# PSU_VCC1V8_Buck.net
KiCad netlist of a schematic drawn in Altium Designer
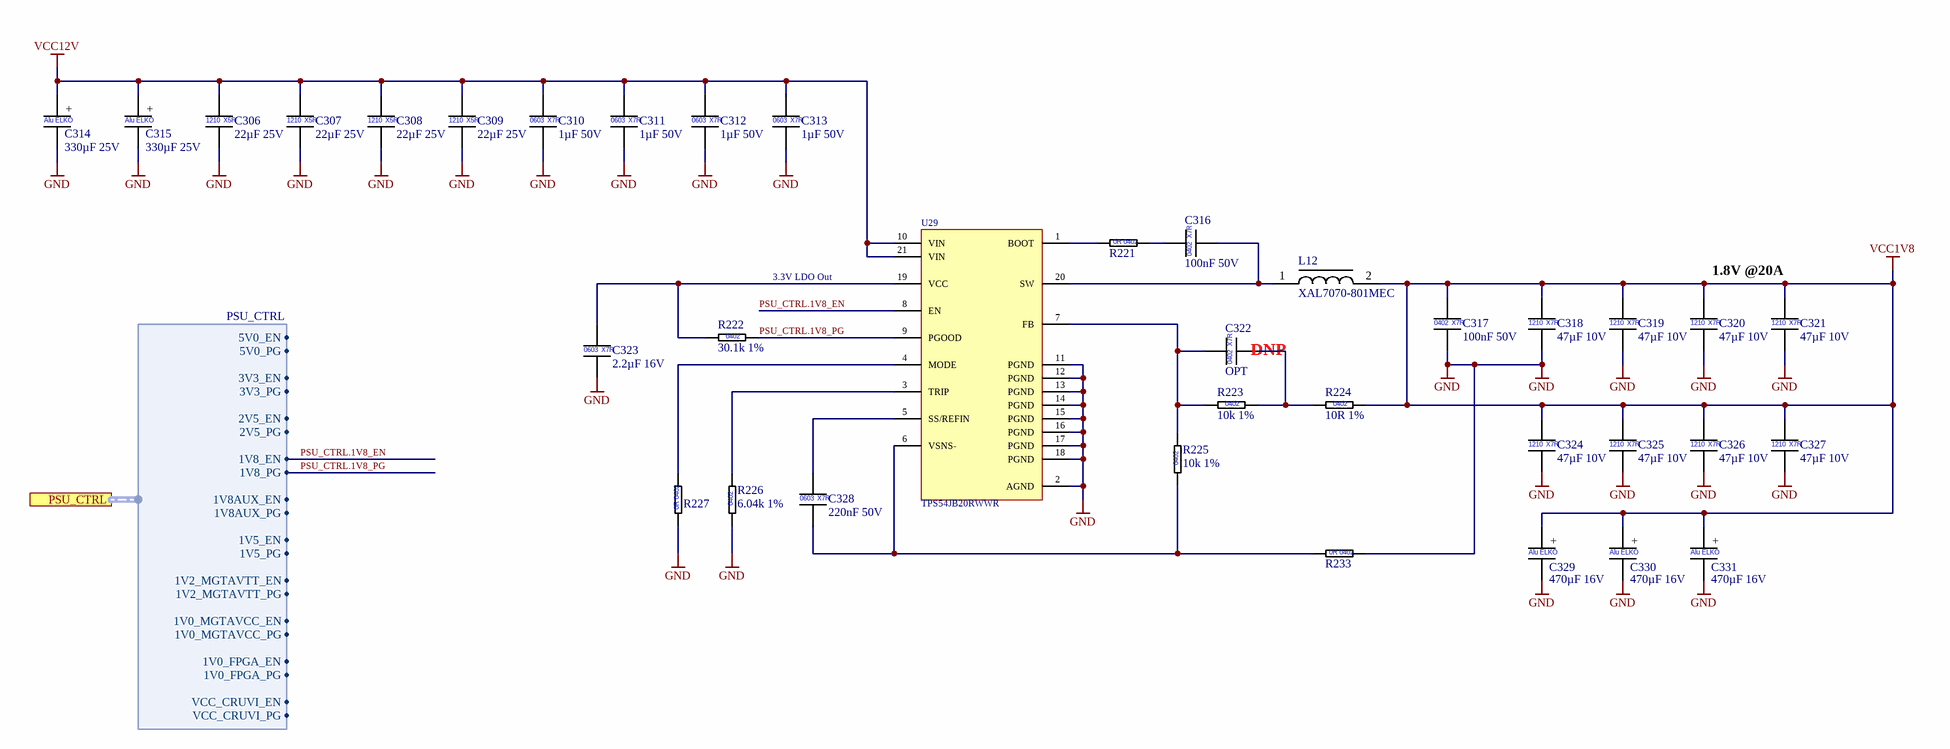
[diagram p0: PSU_VCC1V8_Buck.SchDoc]

(export (version "E")
  (design (tool "Eeschema 10.0.6"))
  (components
    (comp (ref "C306")
      (value "22µF 25V")
      (footprint "Cap:CAP_1210")
      (description "Multilayer Ceramic Capacitors MLCC - SMD/SMT 1210 25VDC")
      (libsource (lib "Cap") (part "CAP_1210_22µF_25V"))
    )
    (comp (ref "C307")
      (value "22µF 25V")
      (footprint "Cap:CAP_1210")
      (description "Multilayer Ceramic Capacitors MLCC - SMD/SMT 1210 25VDC")
      (libsource (lib "Cap") (part "CAP_1210_22µF_25V"))
    )
    (comp (ref "C308")
      (value "22µF 25V")
      (footprint "Cap:CAP_1210")
      (description "Multilayer Ceramic Capacitors MLCC - SMD/SMT 1210 25VDC")
      (libsource (lib "Cap") (part "CAP_1210_22µF_25V"))
    )
    (comp (ref "C309")
      (value "22µF 25V")
      (footprint "Cap:CAP_1210")
      (description "Multilayer Ceramic Capacitors MLCC - SMD/SMT 1210 25VDC")
      (libsource (lib "Cap") (part "CAP_1210_22µF_25V"))
    )
    (comp (ref "C310")
      (value "1µF 50V")
      (footprint "CAP_0603")
      (description "Multilayer Ceramic Capacitors MLCC - SMD/SMT 50V 1uF X7R 0603 10%")
      (libsource (lib "Cap") (part "CAP_0603_1µF_50V_X7R_10%"))
    )
    (comp (ref "C311")
      (value "1µF 50V")
      (footprint "CAP_0603")
      (description "Multilayer Ceramic Capacitors MLCC - SMD/SMT 50V 1uF X7R 0603 10%")
      (libsource (lib "Cap") (part "CAP_0603_1µF_50V_X7R_10%"))
    )
    (comp (ref "C312")
      (value "1µF 50V")
      (footprint "CAP_0603")
      (description "Multilayer Ceramic Capacitors MLCC - SMD/SMT 50V 1uF X7R 0603 10%")
      (libsource (lib "Cap") (part "CAP_0603_1µF_50V_X7R_10%"))
    )
    (comp (ref "C313")
      (value "1µF 50V")
      (footprint "CAP_0603")
      (description "Multilayer Ceramic Capacitors MLCC - SMD/SMT 50V 1uF X7R 0603 10%")
      (libsource (lib "Cap") (part "CAP_0603_1µF_50V_X7R_10%"))
    )
    (comp (ref "C314")
      (value "330µF 25V")
      (footprint "Cap:WCAP-PTG5_D10H12.5")
      (description "Organische Polymer-Aluminiumkondensatoren 330uF 25 Volts 20% AEC-Q200")
      (libsource (lib "Cap") (part "CAP_D10L12.5_330µF_25V"))
    )
    (comp (ref "C315")
      (value "330µF 25V")
      (footprint "Cap:WCAP-PTG5_D10H12.5")
      (description "Organische Polymer-Aluminiumkondensatoren 330uF 25 Volts 20% AEC-Q200")
      (libsource (lib "Cap") (part "CAP_D10L12.5_330µF_25V"))
    )
    (comp (ref "C316")
      (value "100nF 50V")
      (footprint "Cap:CAP_0402")
      (description "Multilayer Ceramic Capacitors MLCC - SMD/SMT 0402 50VDC")
      (libsource (lib "") (part "CAP_0402_100nF_50V_1"))
    )
    (comp (ref "C317")
      (value "100nF 50V")
      (footprint "Cap:CAP_0402")
      (description "Multilayer Ceramic Capacitors MLCC - SMD/SMT 0402 50VDC")
      (libsource (lib "Cap") (part "CAP_0402_100nF_50V"))
    )
    (comp (ref "C318")
      (value "47µF 10V")
      (footprint "Cap:CAP_1210")
      (description "Multilayer Ceramic Capacitors MLCC - SMD/SMT 47 uF 10 VDC 10% 1210 X7R")
      (libsource (lib "Cap") (part "CAP_1210_47µF_10V_X7R_10%"))
    )
    (comp (ref "C319")
      (value "47µF 10V")
      (footprint "Cap:CAP_1210")
      (description "Multilayer Ceramic Capacitors MLCC - SMD/SMT 47 uF 10 VDC 10% 1210 X7R")
      (libsource (lib "Cap") (part "CAP_1210_47µF_10V_X7R_10%"))
    )
    (comp (ref "C320")
      (value "47µF 10V")
      (footprint "Cap:CAP_1210")
      (description "Multilayer Ceramic Capacitors MLCC - SMD/SMT 47 uF 10 VDC 10% 1210 X7R")
      (libsource (lib "Cap") (part "CAP_1210_47µF_10V_X7R_10%"))
    )
    (comp (ref "C321")
      (value "47µF 10V")
      (footprint "Cap:CAP_1210")
      (description "Multilayer Ceramic Capacitors MLCC - SMD/SMT 47 uF 10 VDC 10% 1210 X7R")
      (libsource (lib "Cap") (part "CAP_1210_47µF_10V_X7R_10%"))
    )
    (comp (ref "C322")
      (value "OPT")
      (footprint "Cap:CAP_0402")
      (description "Multilayer Ceramic Capacitors MLCC - SMD/SMT 0402 Optional Placeholder")
      (libsource (lib "Cap") (part "CAP_0402_OPT"))
    )
    (comp (ref "C323")
      (value "2.2µF 16V")
      (footprint "Cap:CAP_0603")
      (description "Multilayer Ceramic Capacitors MLCC - SMD/SMT 2.2 uF 16 VDC 10% 0603 X7R")
      (libsource (lib "Cap") (part "CAP_0603_2.2µF_16V_X7R_10%"))
    )
    (comp (ref "C324")
      (value "47µF 10V")
      (footprint "Cap:CAP_1210")
      (description "Multilayer Ceramic Capacitors MLCC - SMD/SMT 47 uF 10 VDC 10% 1210 X7R")
      (libsource (lib "Cap") (part "CAP_1210_47µF_10V_X7R_10%"))
    )
    (comp (ref "C325")
      (value "47µF 10V")
      (footprint "Cap:CAP_1210")
      (description "Multilayer Ceramic Capacitors MLCC - SMD/SMT 47 uF 10 VDC 10% 1210 X7R")
      (libsource (lib "Cap") (part "CAP_1210_47µF_10V_X7R_10%"))
    )
    (comp (ref "C326")
      (value "47µF 10V")
      (footprint "Cap:CAP_1210")
      (description "Multilayer Ceramic Capacitors MLCC - SMD/SMT 47 uF 10 VDC 10% 1210 X7R")
      (libsource (lib "Cap") (part "CAP_1210_47µF_10V_X7R_10%"))
    )
    (comp (ref "C327")
      (value "47µF 10V")
      (footprint "Cap:CAP_1210")
      (description "Multilayer Ceramic Capacitors MLCC - SMD/SMT 47 uF 10 VDC 10% 1210 X7R")
      (libsource (lib "Cap") (part "CAP_1210_47µF_10V_X7R_10%"))
    )
    (comp (ref "C328")
      (value "220nF 50V")
      (footprint "CAP_0603")
      (description "Multilayer Ceramic Capacitors MLCC - SMD/SMT 0.22 uF 50 VDC 10% 0603 X7R")
      (libsource (lib "Cap") (part "CAP_0603_220nF_50V_X7R_10%"))
    )
    (comp (ref "C329")
      (value "470µF 16V")
      (footprint "Cap:WCAP-PTG5_D8H13")
      (description "Organische Polymer-Aluminiumkondensatoren 470uF 16 Volts 20%")
      (libsource (lib "Cap") (part "CAP_D8L9_470µF_16V"))
    )
    (comp (ref "C330")
      (value "470µF 16V")
      (footprint "Cap:WCAP-PTG5_D8H13")
      (description "Organische Polymer-Aluminiumkondensatoren 470uF 16 Volts 20%")
      (libsource (lib "Cap") (part "CAP_D8L9_470µF_16V"))
    )
    (comp (ref "C331")
      (value "470µF 16V")
      (footprint "Cap:WCAP-PTG5_D8H13")
      (description "Organische Polymer-Aluminiumkondensatoren 470uF 16 Volts 20%")
      (libsource (lib "Cap") (part "CAP_D8L9_470µF_16V"))
    )
    (comp (ref "L12")
      (value "XAL7070-801MEC")
      (footprint "indc:COILCRAFT_XAL7070")
      (description "Power Inductors - SMD 800nH Shld 20% 25.8A 2.29mOhms AECQ200")
      (libsource (lib "Indc") (part "XAL7070-801MEC_Power Inductors SMD 800nH Shld 20% 25.8A 2.29mOhms AECQ200"))
    )
    (comp (ref "R221")
      (value "0R Jumper")
      (footprint "res:RES_0402")
      (description "Thick Film Resistors - SMD 0Ohm")
      (libsource (lib "Res") (part "RES_0402_0R Jumper"))
    )
    (comp (ref "R222")
      (value "30.1k 1%")
      (footprint "res:RES_0402")
      (description "Thick Film Resistors - SMD 30.1kOhm 1%")
      (libsource (lib "Res") (part "RES_0402_30.1k_1%"))
    )
    (comp (ref "R223")
      (value "10k 1%")
      (footprint "Res:RES_0402")
      (description "Thick Film Resistors - SMD 10kOhm 1%")
      (libsource (lib "Res") (part "RES_0402_10k_1%"))
    )
    (comp (ref "R224")
      (value "10R 1%")
      (footprint "res:RES_0402")
      (description "Thick Film Resistors - SMD 10Ohm 1%")
      (libsource (lib "Res") (part "RES_0402_10R_1%"))
    )
    (comp (ref "R225")
      (value "10k 1%")
      (footprint "Res:RES_0402")
      (description "Thick Film Resistors - SMD 10kOhm 1%")
      (libsource (lib "Res") (part "RES_0402_10k_1%"))
    )
    (comp (ref "R226")
      (value "6.04k 1%")
      (footprint "Res:RES_0402")
      (description "Thick Film Resistors - SMD 6.04kOhm 1%")
      (libsource (lib "Res") (part "RES_0402_6.04k_1%"))
    )
    (comp (ref "R227")
      (value "0R Jumper")
      (footprint "res:RES_0402")
      (description "Thick Film Resistors - SMD 0Ohm")
      (libsource (lib "Res") (part "RES_0402_0R Jumper"))
    )
    (comp (ref "R233")
      (value "0R Jumper")
      (footprint "res:RES_0402")
      (description "Thick Film Resistors - SMD 0Ohm")
      (libsource (lib "Res") (part "RES_0402_0R Jumper"))
    )
    (comp (ref "U29")
      (value "TPS54JB20RWWR")
      (footprint "power:VQFN-HR21_RWW0021A")
      (description "Switching Voltage Regulators 2.7-V to 16-V input 20-A synchronous Buck")
      (libsource (lib "Power") (part "TPS54JB20RWWR_Switching Voltage Regulators 2.7-V to 16-V input 20-A synchronous Buck"))
    )
  )
  (nets
    (net (code "2") (name "/PSU_CTRL.1V8_EN") (class "Default")
      (node (ref "U29") (pin "8") (pinfunction "EN_8") (pintype "passive"))
    )
    (net (code "3") (name "/PSU_CTRL.1V8_PG") (class "Default")
      (node (ref "R222") (pin "2") (pinfunction "2_2") (pintype "passive"))
      (node (ref "U29") (pin "9") (pinfunction "PGOOD_9") (pintype "passive"))
    )
    (net (code "5") (name "GND") (class "Default")
      (node (ref "C306") (pin "2") (pinfunction "2_2") (pintype "passive"))
      (node (ref "C307") (pin "2") (pinfunction "2_2") (pintype "passive"))
      (node (ref "C308") (pin "2") (pinfunction "2_2") (pintype "passive"))
      (node (ref "C309") (pin "2") (pinfunction "2_2") (pintype "passive"))
      (node (ref "C310") (pin "2") (pinfunction "2_2") (pintype "passive"))
      (node (ref "C311") (pin "2") (pinfunction "2_2") (pintype "passive"))
      (node (ref "C312") (pin "2") (pinfunction "2_2") (pintype "passive"))
      (node (ref "C313") (pin "2") (pinfunction "2_2") (pintype "passive"))
      (node (ref "C314") (pin "2") (pinfunction "2_2") (pintype "passive"))
      (node (ref "C315") (pin "2") (pinfunction "2_2") (pintype "passive"))
      (node (ref "C317") (pin "2") (pinfunction "2_2") (pintype "passive"))
      (node (ref "C318") (pin "2") (pinfunction "2_2") (pintype "passive"))
      (node (ref "C319") (pin "2") (pinfunction "2_2") (pintype "passive"))
      (node (ref "C320") (pin "2") (pinfunction "2_2") (pintype "passive"))
      (node (ref "C321") (pin "2") (pinfunction "2_2") (pintype "passive"))
      (node (ref "C323") (pin "2") (pinfunction "2_2") (pintype "passive"))
      (node (ref "C324") (pin "2") (pinfunction "2_2") (pintype "passive"))
      (node (ref "C325") (pin "2") (pinfunction "2_2") (pintype "passive"))
      (node (ref "C326") (pin "2") (pinfunction "2_2") (pintype "passive"))
      (node (ref "C327") (pin "2") (pinfunction "2_2") (pintype "passive"))
      (node (ref "C329") (pin "2") (pinfunction "2_2") (pintype "passive"))
      (node (ref "C330") (pin "2") (pinfunction "2_2") (pintype "passive"))
      (node (ref "C331") (pin "2") (pinfunction "2_2") (pintype "passive"))
      (node (ref "R226") (pin "1") (pinfunction "1_1") (pintype "passive"))
      (node (ref "R227") (pin "1") (pinfunction "1_1") (pintype "passive"))
      (node (ref "R233") (pin "2") (pinfunction "2_2") (pintype "passive"))
      (node (ref "U29") (pin "11") (pinfunction "PGND_11") (pintype "passive"))
      (node (ref "U29") (pin "12") (pinfunction "PGND_12") (pintype "passive"))
      (node (ref "U29") (pin "13") (pinfunction "PGND_13") (pintype "passive"))
      (node (ref "U29") (pin "14") (pinfunction "PGND_14") (pintype "passive"))
      (node (ref "U29") (pin "15") (pinfunction "PGND_15") (pintype "passive"))
      (node (ref "U29") (pin "16") (pinfunction "PGND_16") (pintype "passive"))
      (node (ref "U29") (pin "17") (pinfunction "PGND_17") (pintype "passive"))
      (node (ref "U29") (pin "18") (pinfunction "PGND_18") (pintype "passive"))
      (node (ref "U29") (pin "2") (pinfunction "AGND_2") (pintype "passive"))
    )
    (net (code "6") (name "Net-(C316-Pad1)") (class "Default")
      (node (ref "C316") (pin "1") (pinfunction "1_1") (pintype "passive"))
      (node (ref "R221") (pin "2") (pinfunction "2_2") (pintype "passive"))
    )
    (net (code "7") (name "Net-(C322-Pad2)") (class "Default")
      (node (ref "C322") (pin "2") (pinfunction "2_2") (pintype "passive"))
      (node (ref "R223") (pin "2") (pinfunction "2_2") (pintype "passive"))
      (node (ref "R224") (pin "1") (pinfunction "1_1") (pintype "passive"))
    )
    (net (code "8") (name "Net-(U29-BOOT)") (class "Default")
      (node (ref "R221") (pin "1") (pinfunction "1_1") (pintype "passive"))
      (node (ref "U29") (pin "1") (pinfunction "BOOT_1") (pintype "passive"))
    )
    (net (code "9") (name "Net-(U29-FB)") (class "Default")
      (node (ref "C322") (pin "1") (pinfunction "1_1") (pintype "passive"))
      (node (ref "R223") (pin "1") (pinfunction "1_1") (pintype "passive"))
      (node (ref "R225") (pin "2") (pinfunction "2_2") (pintype "passive"))
      (node (ref "U29") (pin "7") (pinfunction "FB_7") (pintype "passive"))
    )
    (net (code "10") (name "Net-(U29-MODE)") (class "Default")
      (node (ref "R227") (pin "2") (pinfunction "2_2") (pintype "passive"))
      (node (ref "U29") (pin "4") (pinfunction "MODE_4") (pintype "passive"))
    )
    (net (code "11") (name "Net-(U29-SS{slash}REFIN)") (class "Default")
      (node (ref "C328") (pin "1") (pinfunction "1_1") (pintype "passive"))
      (node (ref "U29") (pin "5") (pinfunction "SS/REFIN_5") (pintype "passive"))
    )
    (net (code "12") (name "Net-(U29-SW)") (class "Default")
      (node (ref "C316") (pin "2") (pinfunction "2_2") (pintype "passive"))
      (node (ref "L12") (pin "1") (pinfunction "1_1") (pintype "passive"))
      (node (ref "U29") (pin "20") (pinfunction "SW_20") (pintype "passive"))
    )
    (net (code "13") (name "Net-(U29-TRIP)") (class "Default")
      (node (ref "R226") (pin "2") (pinfunction "2_2") (pintype "passive"))
      (node (ref "U29") (pin "3") (pinfunction "TRIP_3") (pintype "passive"))
    )
    (net (code "14") (name "Net-(U29-VCC)") (class "Default")
      (node (ref "C323") (pin "1") (pinfunction "1_1") (pintype "passive"))
      (node (ref "R222") (pin "1") (pinfunction "1_1") (pintype "passive"))
      (node (ref "U29") (pin "19") (pinfunction "VCC_19") (pintype "passive"))
    )
    (net (code "15") (name "Net-(U29-VSNS-)") (class "Default")
      (node (ref "C328") (pin "2") (pinfunction "2_2") (pintype "passive"))
      (node (ref "R225") (pin "1") (pinfunction "1_1") (pintype "passive"))
      (node (ref "R233") (pin "1") (pinfunction "1_1") (pintype "passive"))
      (node (ref "U29") (pin "6") (pinfunction "VSNS-_6") (pintype "passive"))
    )
    (net (code "16") (name "VCC1V8") (class "Default")
      (node (ref "C317") (pin "1") (pinfunction "1_1") (pintype "passive"))
      (node (ref "C318") (pin "1") (pinfunction "1_1") (pintype "passive"))
      (node (ref "C319") (pin "1") (pinfunction "1_1") (pintype "passive"))
      (node (ref "C320") (pin "1") (pinfunction "1_1") (pintype "passive"))
      (node (ref "C321") (pin "1") (pinfunction "1_1") (pintype "passive"))
      (node (ref "C324") (pin "1") (pinfunction "1_1") (pintype "passive"))
      (node (ref "C325") (pin "1") (pinfunction "1_1") (pintype "passive"))
      (node (ref "C326") (pin "1") (pinfunction "1_1") (pintype "passive"))
      (node (ref "C327") (pin "1") (pinfunction "1_1") (pintype "passive"))
      (node (ref "C329") (pin "1") (pinfunction "1_1") (pintype "passive"))
      (node (ref "C330") (pin "1") (pinfunction "1_1") (pintype "passive"))
      (node (ref "C331") (pin "1") (pinfunction "1_1") (pintype "passive"))
      (node (ref "L12") (pin "2") (pinfunction "2_2") (pintype "passive"))
      (node (ref "R224") (pin "2") (pinfunction "2_2") (pintype "passive"))
    )
    (net (code "17") (name "VCC12V") (class "Default")
      (node (ref "C306") (pin "1") (pinfunction "1_1") (pintype "passive"))
      (node (ref "C307") (pin "1") (pinfunction "1_1") (pintype "passive"))
      (node (ref "C308") (pin "1") (pinfunction "1_1") (pintype "passive"))
      (node (ref "C309") (pin "1") (pinfunction "1_1") (pintype "passive"))
      (node (ref "C310") (pin "1") (pinfunction "1_1") (pintype "passive"))
      (node (ref "C311") (pin "1") (pinfunction "1_1") (pintype "passive"))
      (node (ref "C312") (pin "1") (pinfunction "1_1") (pintype "passive"))
      (node (ref "C313") (pin "1") (pinfunction "1_1") (pintype "passive"))
      (node (ref "C314") (pin "1") (pinfunction "1_1") (pintype "passive"))
      (node (ref "C315") (pin "1") (pinfunction "1_1") (pintype "passive"))
      (node (ref "U29") (pin "10") (pinfunction "VIN_10") (pintype "passive"))
      (node (ref "U29") (pin "21") (pinfunction "VIN_21") (pintype "passive"))
    )
  )
)
